# Stepper_Driver_Quark.net
KiCad netlist of a schematic drawn in Altium Designer
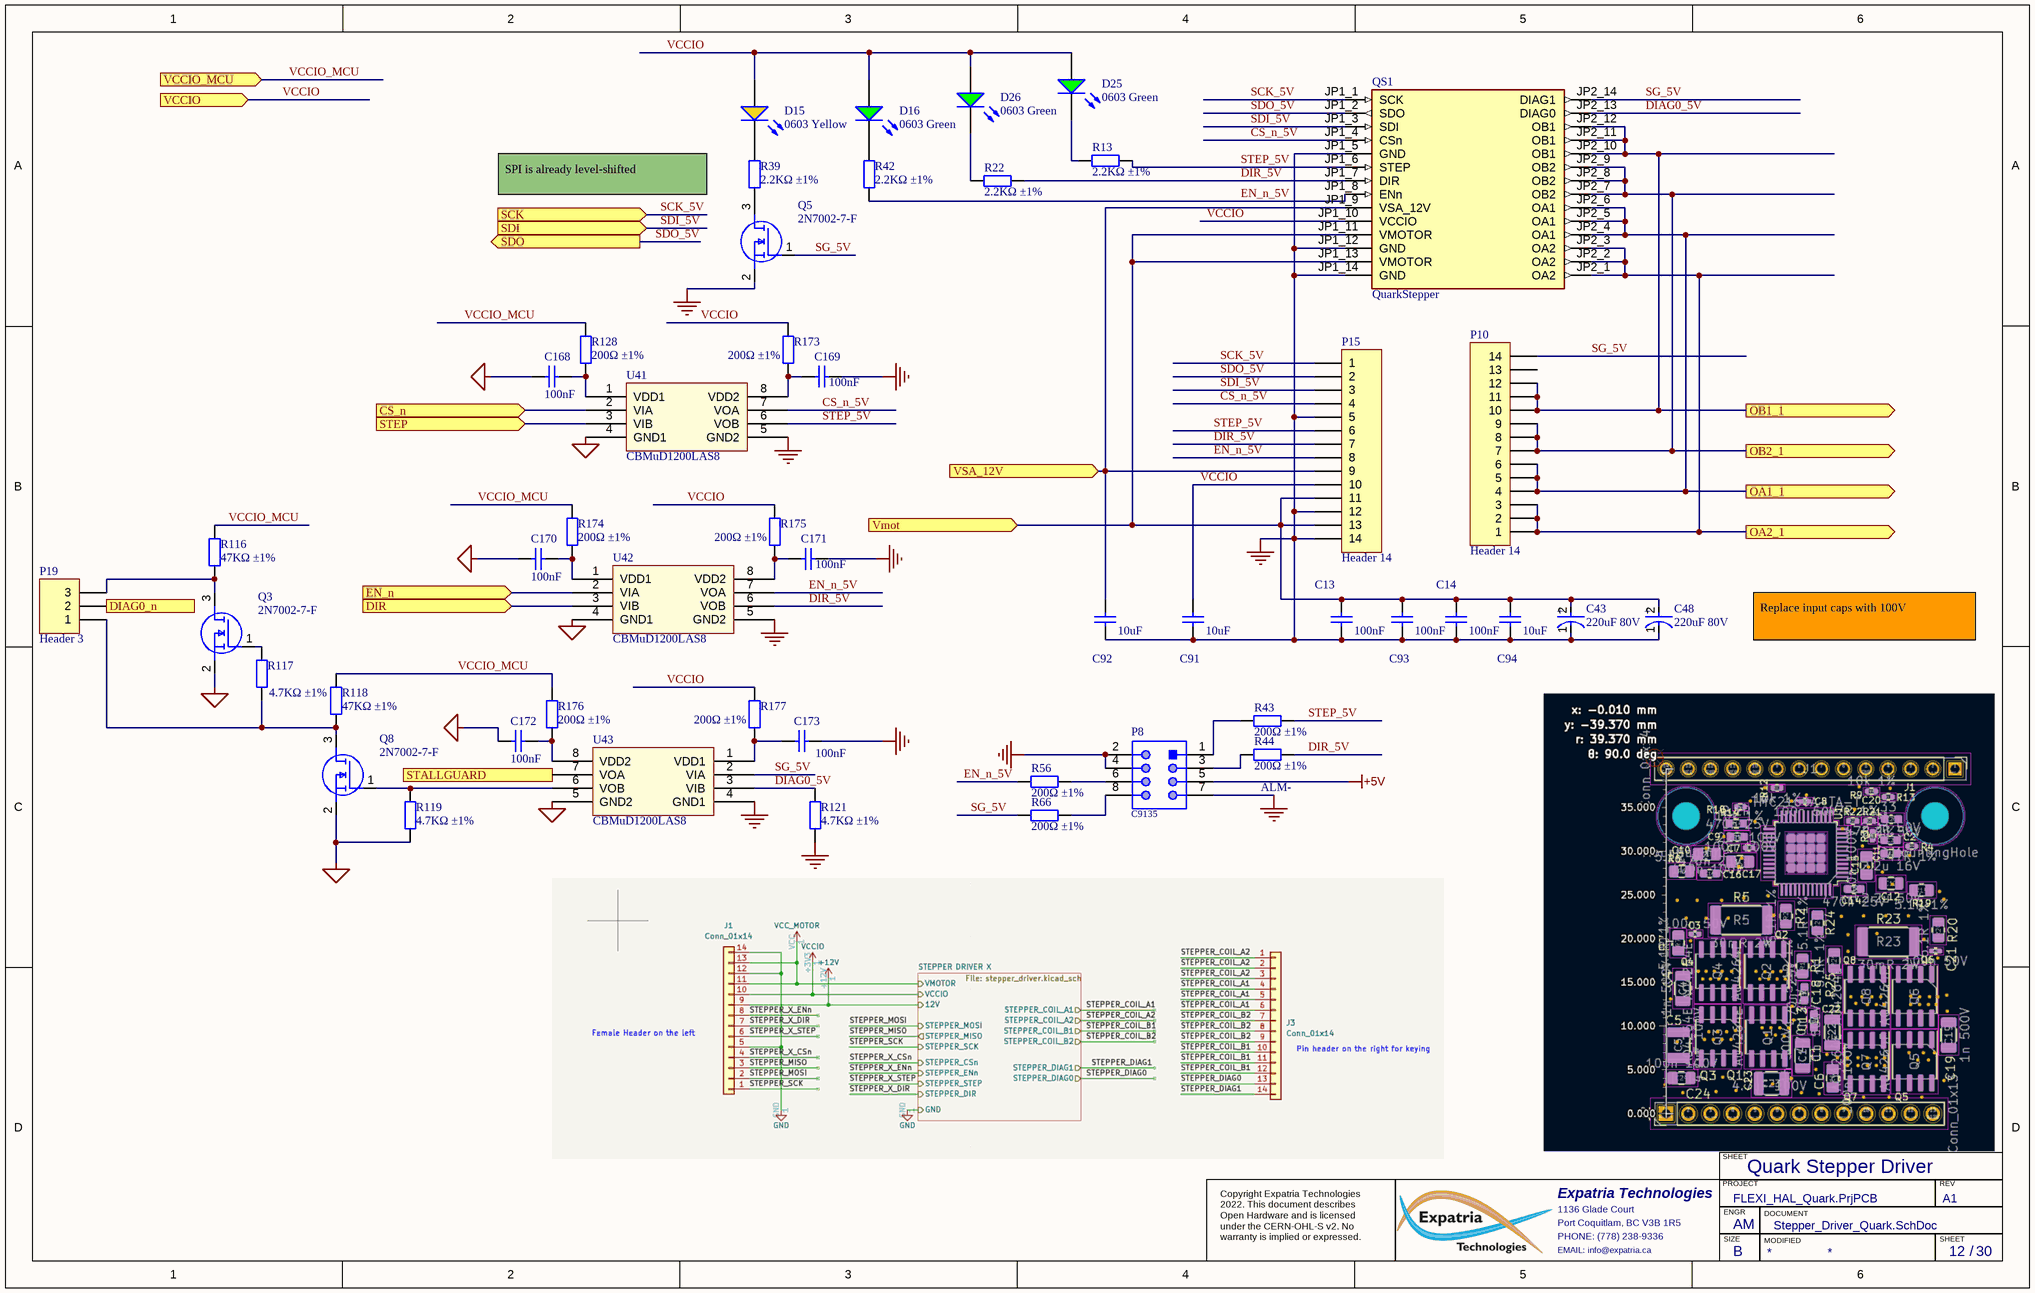
[diagram p0: Stepper_Driver_Quark.SchDoc]

(export (version "E")
  (design (tool "Eeschema 10.0.6"))
  (components
    (comp (ref "C13")
      (value "100nF")
      (footprint "0603_C")
      (description "Chip capacitors")
      (fields
        (field (name "MANUFACTURER") "YAGEO")
        (field (name "MANUFACTURER PART NUMBER") "CC0603KRX7R9BB104")
      )
      (libsource (lib "Cap") (part "0603 100nF (104) 10% 50V"))
    )
    (comp (ref "C14")
      (value "100nF")
      (footprint "0603_C")
      (description "Chip capacitors")
      (fields
        (field (name "MANUFACTURER") "YAGEO")
        (field (name "MANUFACTURER PART NUMBER") "CC0603KRX7R9BB104")
      )
      (libsource (lib "Cap") (part "0603 100nF (104) 10% 50V"))
    )
    (comp (ref "C43")
      (value "220uF 80V")
      (footprint "FP-RAD-TH-D_10_0_5-L_20_2-MFG")
      (description "Aluminum Electrolytic Capacitors (Radial Lead Type) AEC-Q200 Qualified 820uF ±20% 25V")
      (fields (field (name "TOLERANCE") "20%") (field (name "VOLTAGE") "25V"))
      (libsource (lib "Altium Content Vault") (part "203bc49f2ac43e59fd269a8c329ed05"))
    )
    (comp (ref "C48")
      (value "220uF 80V")
      (footprint "FP-RAD-TH-D_10_0_5-L_20_2-MFG")
      (description "Aluminum Electrolytic Capacitors (Radial Lead Type) AEC-Q200 Qualified 820uF ±20% 25V")
      (fields (field (name "TOLERANCE") "20%") (field (name "VOLTAGE") "25V"))
      (libsource (lib "Altium Content Vault") (part "203bc49f2ac43e59fd269a8c329ed05"))
    )
    (comp (ref "C91")
      (value "10uF")
      (footprint "0805_C")
      (description "Chip capacitors")
      (fields
        (field (name "MANUFACTURER") "Samsung Electro-Mechanics")
        (field (name "PARTNUMBER") "CL21A106KAYNNNE")
      )
      (libsource (lib "Cap") (part "0805 10uF (106) 10% 25V"))
    )
    (comp (ref "C92")
      (value "10uF")
      (footprint "0805_C")
      (description "Chip capacitors")
      (fields
        (field (name "MANUFACTURER") "Samsung Electro-Mechanics")
        (field (name "PARTNUMBER") "CL21A106KAYNNNE")
      )
      (libsource (lib "Cap") (part "0805 10uF (106) 10% 25V"))
    )
    (comp (ref "C93")
      (value "100nF")
      (footprint "0603_C")
      (description "Chip capacitors")
      (fields
        (field (name "MANUFACTURER") "YAGEO")
        (field (name "MANUFACTURER PART NUMBER") "CC0603KRX7R9BB104")
      )
      (libsource (lib "Cap") (part "0603 100nF (104) 10% 50V"))
    )
    (comp (ref "C94")
      (value "10uF")
      (footprint "0805_C")
      (description "Chip capacitors")
      (fields
        (field (name "MANUFACTURER") "Samsung Electro-Mechanics")
        (field (name "PARTNUMBER") "CL21A106KAYNNNE")
      )
      (libsource (lib "Cap") (part "0805 10uF (106) 10% 25V"))
    )
    (comp (ref "C168")
      (value "100nF")
      (footprint "0603_C")
      (description "Chip capacitors")
      (fields (field (name "MANUFACTURER") "YAGEO") (field (name "PARTNUMBER") "CC0603KRX7R9BB104"))
      (libsource (lib "Cap") (part "0603 100nF (104) 10% 50V"))
    )
    (comp (ref "C169")
      (value "100nF")
      (footprint "0603_C")
      (description "Chip capacitors")
      (fields (field (name "MANUFACTURER") "YAGEO") (field (name "PARTNUMBER") "CC0603KRX7R9BB104"))
      (libsource (lib "Cap") (part "0603 100nF (104) 10% 50V"))
    )
    (comp (ref "C170")
      (value "100nF")
      (footprint "0603_C")
      (description "Chip capacitors")
      (fields (field (name "MANUFACTURER") "YAGEO") (field (name "PARTNUMBER") "CC0603KRX7R9BB104"))
      (libsource (lib "Cap") (part "0603 100nF (104) 10% 50V"))
    )
    (comp (ref "C171")
      (value "100nF")
      (footprint "0603_C")
      (description "Chip capacitors")
      (fields (field (name "MANUFACTURER") "YAGEO") (field (name "PARTNUMBER") "CC0603KRX7R9BB104"))
      (libsource (lib "Cap") (part "0603 100nF (104) 10% 50V"))
    )
    (comp (ref "C172")
      (value "100nF")
      (footprint "0603_C")
      (description "Chip capacitors")
      (fields (field (name "MANUFACTURER") "YAGEO") (field (name "PARTNUMBER") "CC0603KRX7R9BB104"))
      (libsource (lib "Cap") (part "0603 100nF (104) 10% 50V"))
    )
    (comp (ref "C173")
      (value "100nF")
      (footprint "0603_C")
      (description "Chip capacitors")
      (fields (field (name "MANUFACTURER") "YAGEO") (field (name "PARTNUMBER") "CC0603KRX7R9BB104"))
      (libsource (lib "Cap") (part "0603 100nF (104) 10% 50V"))
    )
    (comp (ref "D15")
      (value "0603 Yellow")
      (footprint "0603_LED_S1")
      (description "LED")
      (libsource (lib "LED") (part "0603 LED Yellow"))
    )
    (comp (ref "D16")
      (value "0603 Green")
      (footprint "0603_LED_S1")
      (description "LED")
      (libsource (lib "LED") (part "0603 LED Green"))
    )
    (comp (ref "D25")
      (value "0603 Green")
      (footprint "0603_LED_S1")
      (description "LED")
      (libsource (lib "LED") (part "0603 LED Green"))
    )
    (comp (ref "D26")
      (value "0603 Green")
      (footprint "0603_LED_S1")
      (description "LED")
      (libsource (lib "LED") (part "0603 LED Green"))
    )
    (comp (ref "P8")
      (value "C9135")
      (footprint "61200821621")
      (description "Male Box Header WR-BHD, THT, Vertical, pitch 2.54 mm, 8 pins")
      (fields (field (name "MANUFACTURER") "Wurth Elektronik") (field (name "PUBLISHER") "WurthElektronik"))
      (libsource (lib "PrintNC_GRBLHAL_Breakout") (part "WE-CN-2P-M-R8"))
    )
    (comp (ref "P10")
      (value "Header 14")
      (footprint "HDR1X14")
      (description "Header, 14-Pin")
      (fields (field (name "PUBLISHER") "Altium Limited"))
      (libsource (lib "Miscellaneous Connectors") (part "Header 14"))
    )
    (comp (ref "P15")
      (value "Header 14")
      (footprint "HDR1X14")
      (description "Socket, 14-Pin")
      (fields (field (name "PUBLISHER") "Altium Limited"))
      (libsource (lib "") (part "Header 14_1"))
    )
    (comp (ref "P19")
      (value "Header 3")
      (footprint "HDR1X3")
      (description "Header, 3-Pin")
      (fields (field (name "PUBLISHER") "Altium Limited"))
      (libsource (lib "Miscellaneous Connectors") (part "Header 3"))
    )
    (comp (ref "Q3")
      (value "2N7002-7-F")
      (footprint "SOT-23(SOT-23-3)")
      (description "60V 115mA 7.5Ω@5V,50mA 370mW N Channel SOT-23 MOSFETs ROHS")
      (fields (field (name "MANUFACTURER") "Diodes Inc.") (field (name "MOUSER PART NUMBER") "621-2N7002-F"))
      (libsource (lib "Sienci_Labs") (part "2N7002-7-F"))
    )
    (comp (ref "Q5")
      (value "2N7002-7-F")
      (footprint "SOT-23(SOT-23-3)")
      (description "60V 115mA 7.5Ω@5V,50mA 370mW N Channel SOT-23 MOSFETs ROHS")
      (fields (field (name "MANUFACTURER") "Diodes Inc.") (field (name "MOUSER PART NUMBER") "621-2N7002-F"))
      (libsource (lib "Sienci_Labs") (part "2N7002-7-F"))
    )
    (comp (ref "Q8")
      (value "2N7002-7-F")
      (footprint "SOT-23(SOT-23-3)")
      (description "60V 115mA 7.5Ω@5V,50mA 370mW N Channel SOT-23 MOSFETs ROHS")
      (fields (field (name "MANUFACTURER") "Diodes Inc.") (field (name "MOUSER PART NUMBER") "621-2N7002-F"))
      (libsource (lib "Sienci_Labs") (part "2N7002-7-F"))
    )
    (comp (ref "QS1")
      (value "QuarkStepper")
      (footprint "QuarkStepperDriver")
      (description "Open source TMC2160 module")
      (fields
        (field (name "DIGI-KEY_PART_NUMBER") "1460-TMC2208SILENTSTEPSTICK-ND")
        (field (name "MF") "Trinamic Motion")
      )
      (libsource (lib "Universal_CNC_Breakout") (part "Quark_2160"))
    )
    (comp (ref "R13")
      (value "2.2KΩ ±1%")
      (footprint "0603_R")
      (description "Chip resistor")
      (fields (field (name "MANUFACTURER") "Uniroyal Elec") (field (name "POWER") "1/10W"))
      (libsource (lib "") (part "0603 2.2K (2201) 1%_1"))
    )
    (comp (ref "R22")
      (value "2.2KΩ ±1%")
      (footprint "0603_R")
      (description "Chip resistor")
      (fields (field (name "MANUFACTURER") "Uniroyal Elec") (field (name "POWER") "1/10W"))
      (libsource (lib "") (part "0603 2.2K (2201) 1%_1"))
    )
    (comp (ref "R39")
      (value "2.2KΩ ±1%")
      (footprint "0603_R")
      (description "Chip resistor")
      (fields (field (name "MANUFACTURER") "Uniroyal Elec") (field (name "POWER") "1/10W"))
      (libsource (lib "RES") (part "0603 2.2K (2201) 1%"))
    )
    (comp (ref "R42")
      (value "2.2KΩ ±1%")
      (footprint "0603_R")
      (description "Chip resistor")
      (fields (field (name "MANUFACTURER") "Uniroyal Elec") (field (name "POWER") "1/10W"))
      (libsource (lib "RES") (part "0603 2.2K (2201) 1%"))
    )
    (comp (ref "R43")
      (value "200Ω ±1%")
      (footprint "0603_R")
      (description "Chip resistor")
      (fields (field (name "MANUFACTURER") "Uniroyal Elec") (field (name "PARTNUMBER") "0603WAF2000T5E"))
      (libsource (lib "") (part "0603 200R (2000) 1%_1"))
    )
    (comp (ref "R44")
      (value "200Ω ±1%")
      (footprint "0603_R")
      (description "Chip resistor")
      (fields (field (name "MANUFACTURER") "Uniroyal Elec") (field (name "PARTNUMBER") "0603WAF2000T5E"))
      (libsource (lib "") (part "0603 200R (2000) 1%_1"))
    )
    (comp (ref "R56")
      (value "200Ω ±1%")
      (footprint "0603_R")
      (description "Chip resistor")
      (fields (field (name "MANUFACTURER") "Uniroyal Elec") (field (name "PARTNUMBER") "0603WAF2000T5E"))
      (libsource (lib "") (part "0603 200R (2000) 1%_1"))
    )
    (comp (ref "R66")
      (value "200Ω ±1%")
      (footprint "0603_R")
      (description "Chip resistor")
      (fields (field (name "MANUFACTURER") "Uniroyal Elec") (field (name "PARTNUMBER") "0603WAF2000T5E"))
      (libsource (lib "") (part "0603 200R (2000) 1%_1"))
    )
    (comp (ref "R116")
      (value "47KΩ ±1%")
      (footprint "0603_R")
      (description "Chip resistor")
      (fields (field (name "MANUFACTURER") "Uniroyal Elec") (field (name "PARTNUMBER") "0603WAF4702T5E"))
      (libsource (lib "RES") (part "0603 47K (4702) 1%"))
    )
    (comp (ref "R117")
      (value "4.7KΩ ±1%")
      (footprint "0603_R")
      (description "Chip resistor")
      (fields (field (name "MANUFACTURER") "Uniroyal Elec") (field (name "PARTNUMBER") "0603WAF4701T5E"))
      (libsource (lib "RES") (part "0603 4.7K (4701) 1%"))
    )
    (comp (ref "R118")
      (value "47KΩ ±1%")
      (footprint "0603_R")
      (description "Chip resistor")
      (fields (field (name "MANUFACTURER") "Uniroyal Elec") (field (name "PARTNUMBER") "0603WAF4702T5E"))
      (libsource (lib "RES") (part "0603 47K (4702) 1%"))
    )
    (comp (ref "R119")
      (value "4.7KΩ ±1%")
      (footprint "0603_R")
      (description "Chip resistor")
      (fields (field (name "MANUFACTURER") "Uniroyal Elec") (field (name "PARTNUMBER") "0603WAF4701T5E"))
      (libsource (lib "RES") (part "0603 4.7K (4701) 1%"))
    )
    (comp (ref "R121")
      (value "4.7KΩ ±1%")
      (footprint "0603_R")
      (description "Chip resistor")
      (fields (field (name "MANUFACTURER") "Uniroyal Elec") (field (name "PARTNUMBER") "0603WAF4701T5E"))
      (libsource (lib "RES") (part "0603 4.7K (4701) 1%"))
    )
    (comp (ref "R128")
      (value "200Ω ±1%")
      (footprint "0603_R")
      (description "Chip resistor")
      (fields (field (name "MANUFACTURER") "Uniroyal Elec") (field (name "PARTNUMBER") "0603WAF2000T5E"))
      (libsource (lib "RES") (part "0603 200R (2000) 1%"))
    )
    (comp (ref "R173")
      (value "200Ω ±1%")
      (footprint "0603_R")
      (description "Chip resistor")
      (fields (field (name "MANUFACTURER") "Uniroyal Elec") (field (name "PARTNUMBER") "0603WAF2000T5E"))
      (libsource (lib "RES") (part "0603 200R (2000) 1%"))
    )
    (comp (ref "R174")
      (value "200Ω ±1%")
      (footprint "0603_R")
      (description "Chip resistor")
      (fields (field (name "MANUFACTURER") "Uniroyal Elec") (field (name "PARTNUMBER") "0603WAF2000T5E"))
      (libsource (lib "RES") (part "0603 200R (2000) 1%"))
    )
    (comp (ref "R175")
      (value "200Ω ±1%")
      (footprint "0603_R")
      (description "Chip resistor")
      (fields (field (name "MANUFACTURER") "Uniroyal Elec") (field (name "PARTNUMBER") "0603WAF2000T5E"))
      (libsource (lib "RES") (part "0603 200R (2000) 1%"))
    )
    (comp (ref "R176")
      (value "200Ω ±1%")
      (footprint "0603_R")
      (description "Chip resistor")
      (fields (field (name "MANUFACTURER") "Uniroyal Elec") (field (name "PARTNUMBER") "0603WAF2000T5E"))
      (libsource (lib "") (part "0603 200R (2000) 1%_2"))
    )
    (comp (ref "R177")
      (value "200Ω ±1%")
      (footprint "0603_R")
      (description "Chip resistor")
      (fields (field (name "MANUFACTURER") "Uniroyal Elec") (field (name "PARTNUMBER") "0603WAF2000T5E"))
      (libsource (lib "") (part "0603 200R (2000) 1%_2"))
    )
    (comp (ref "U41")
      (value "CBMuD1200LAS8")
      (footprint "SOIC-8_150mil")
      (description "Dual Channel Isolator")
      (libsource (lib "IC") (part "CBMuD1200LAS8"))
    )
    (comp (ref "U42")
      (value "CBMuD1200LAS8")
      (footprint "SOIC-8_150mil")
      (description "Dual Channel Isolator")
      (libsource (lib "IC") (part "CBMuD1200LAS8"))
    )
    (comp (ref "U43")
      (value "CBMuD1200LAS8")
      (footprint "SOIC-8_150mil")
      (description "Dual Channel Isolator")
      (libsource (lib "") (part "CBMuD1200LAS8_1"))
    )
  )
  (nets
    (net (code "1") (name "+5V") (class "Default")
      (node (ref "P8") (pin "5") (pinfunction "5_5") (pintype "passive"))
    )
    (net (code "2") (name "/CS_n") (class "Default")
      (node (ref "U41") (pin "2") (pinfunction "VIA_2") (pintype "passive"))
    )
    (net (code "3") (name "/CS_n_5V") (class "Default")
      (node (ref "P15") (pin "4") (pinfunction "4_4") (pintype "passive"))
      (node (ref "QS1") (pin "JP1_4") (pinfunction "CSn_JP1_4") (pintype "input"))
      (node (ref "U41") (pin "7") (pinfunction "VOA_7") (pintype "passive"))
    )
    (net (code "4") (name "/DIAG0_5V") (class "Default")
      (node (ref "QS1") (pin "JP2_13") (pinfunction "DIAG0_JP2_13") (pintype "output"))
      (node (ref "R121") (pin "2") (pinfunction "2_2") (pintype "passive"))
      (node (ref "U43") (pin "3") (pinfunction "VIB_3") (pintype "passive"))
    )
    (net (code "5") (name "/DIAG0_n") (class "Default")
      (node (ref "P19") (pin "2") (pinfunction "2_2") (pintype "passive"))
    )
    (net (code "6") (name "/DIR") (class "Default")
      (node (ref "U42") (pin "3") (pinfunction "VIB_3") (pintype "passive"))
    )
    (net (code "7") (name "/DIR_5V") (class "Default")
      (node (ref "P15") (pin "7") (pinfunction "7_7") (pintype "passive"))
      (node (ref "QS1") (pin "JP1_7") (pinfunction "DIR_JP1_7") (pintype "input"))
      (node (ref "R22") (pin "1") (pinfunction "1_1") (pintype "passive"))
      (node (ref "R44") (pin "1") (pinfunction "1_1") (pintype "passive"))
      (node (ref "U42") (pin "6") (pinfunction "VOB_6") (pintype "passive"))
    )
    (net (code "8") (name "/EN_n") (class "Default")
      (node (ref "U42") (pin "2") (pinfunction "VIA_2") (pintype "passive"))
    )
    (net (code "9") (name "/EN_n_5V") (class "Default")
      (node (ref "P15") (pin "8") (pinfunction "8_8") (pintype "passive"))
      (node (ref "QS1") (pin "JP1_8") (pinfunction "ENn_JP1_8") (pintype "input"))
      (node (ref "R42") (pin "1") (pinfunction "1_1") (pintype "passive"))
      (node (ref "R56") (pin "2") (pinfunction "2_2") (pintype "passive"))
      (node (ref "U42") (pin "7") (pinfunction "VOA_7") (pintype "passive"))
    )
    (net (code "10") (name "/OA1_1") (class "Default")
      (node (ref "P10") (pin "4") (pinfunction "4_4") (pintype "passive"))
      (node (ref "P10") (pin "5") (pinfunction "5_5") (pintype "passive"))
      (node (ref "P10") (pin "6") (pinfunction "6_6") (pintype "passive"))
      (node (ref "QS1") (pin "JP2_4") (pinfunction "OA1_JP2_4") (pintype "output"))
      (node (ref "QS1") (pin "JP2_5") (pinfunction "OA1_JP2_5") (pintype "output"))
      (node (ref "QS1") (pin "JP2_6") (pinfunction "OA1_JP2_6") (pintype "output"))
    )
    (net (code "11") (name "/OA2_1") (class "Default")
      (node (ref "P10") (pin "1") (pinfunction "1_1") (pintype "passive"))
      (node (ref "P10") (pin "2") (pinfunction "2_2") (pintype "passive"))
      (node (ref "P10") (pin "3") (pinfunction "3_3") (pintype "passive"))
      (node (ref "QS1") (pin "JP2_1") (pinfunction "OA2_JP2_1") (pintype "output"))
      (node (ref "QS1") (pin "JP2_2") (pinfunction "OA2_JP2_2") (pintype "output"))
      (node (ref "QS1") (pin "JP2_3") (pinfunction "OA2_JP2_3") (pintype "output"))
    )
    (net (code "12") (name "/OB1_1") (class "Default")
      (node (ref "P10") (pin "10") (pinfunction "10_10") (pintype "passive"))
      (node (ref "P10") (pin "11") (pinfunction "11_11") (pintype "passive"))
      (node (ref "P10") (pin "12") (pinfunction "12_12") (pintype "passive"))
      (node (ref "QS1") (pin "JP2_10") (pinfunction "OB1_JP2_10") (pintype "output"))
      (node (ref "QS1") (pin "JP2_11") (pinfunction "OB1_JP2_11") (pintype "output"))
      (node (ref "QS1") (pin "JP2_12") (pinfunction "OB1_JP2_12") (pintype "output"))
    )
    (net (code "13") (name "/OB2_1") (class "Default")
      (node (ref "P10") (pin "7") (pinfunction "7_7") (pintype "passive"))
      (node (ref "P10") (pin "8") (pinfunction "8_8") (pintype "passive"))
      (node (ref "P10") (pin "9") (pinfunction "9_9") (pintype "passive"))
      (node (ref "QS1") (pin "JP2_7") (pinfunction "OB2_JP2_7") (pintype "output"))
      (node (ref "QS1") (pin "JP2_8") (pinfunction "OB2_JP2_8") (pintype "output"))
      (node (ref "QS1") (pin "JP2_9") (pinfunction "OB2_JP2_9") (pintype "output"))
    )
    (net (code "14") (name "/SCK_5V") (class "Default")
      (node (ref "P15") (pin "1") (pinfunction "1_1") (pintype "passive"))
      (node (ref "QS1") (pin "JP1_1") (pinfunction "SCK_JP1_1") (pintype "input"))
    )
    (net (code "15") (name "/SDI_5V") (class "Default")
      (node (ref "P15") (pin "3") (pinfunction "3_3") (pintype "passive"))
      (node (ref "QS1") (pin "JP1_3") (pinfunction "SDI_JP1_3") (pintype "input"))
    )
    (net (code "16") (name "/SDO_5V") (class "Default")
      (node (ref "P15") (pin "2") (pinfunction "2_2") (pintype "passive"))
      (node (ref "QS1") (pin "JP1_2") (pinfunction "SDO_JP1_2") (pintype "output"))
    )
    (net (code "17") (name "/SG_5V") (class "Default")
      (node (ref "P10") (pin "14") (pinfunction "14_14") (pintype "passive"))
      (node (ref "Q5") (pin "1") (pinfunction "G_1") (pintype "passive"))
      (node (ref "QS1") (pin "JP2_14") (pinfunction "DIAG1_JP2_14") (pintype "output"))
      (node (ref "R66") (pin "2") (pinfunction "2_2") (pintype "passive"))
      (node (ref "U43") (pin "2") (pinfunction "VIA_2") (pintype "passive"))
    )
    (net (code "18") (name "/STALLGUARD") (class "Default")
      (node (ref "U43") (pin "7") (pinfunction "VOA_7") (pintype "passive"))
    )
    (net (code "19") (name "/STEP") (class "Default")
      (node (ref "U41") (pin "3") (pinfunction "VIB_3") (pintype "passive"))
    )
    (net (code "20") (name "/STEP_5V") (class "Default")
      (node (ref "P15") (pin "6") (pinfunction "6_6") (pintype "passive"))
      (node (ref "QS1") (pin "JP1_6") (pinfunction "STEP_JP1_6") (pintype "input"))
      (node (ref "R13") (pin "1") (pinfunction "1_1") (pintype "passive"))
      (node (ref "R43") (pin "1") (pinfunction "1_1") (pintype "passive"))
      (node (ref "U41") (pin "6") (pinfunction "VOB_6") (pintype "passive"))
    )
    (net (code "21") (name "/VCCIO") (class "Default")
      (node (ref "C91") (pin "2") (pinfunction "2_2") (pintype "passive"))
      (node (ref "D15") (pin "A") (pinfunction "A_A") (pintype "passive"))
      (node (ref "D16") (pin "A") (pinfunction "A_A") (pintype "passive"))
      (node (ref "D25") (pin "A") (pinfunction "A_A") (pintype "passive"))
      (node (ref "D26") (pin "A") (pinfunction "A_A") (pintype "passive"))
      (node (ref "P15") (pin "10") (pinfunction "10_10") (pintype "passive"))
      (node (ref "QS1") (pin "JP1_10") (pinfunction "VCCIO_JP1_10") (pintype "passive"))
      (node (ref "R173") (pin "2") (pinfunction "2_2") (pintype "passive"))
      (node (ref "R175") (pin "2") (pinfunction "2_2") (pintype "passive"))
      (node (ref "R177") (pin "2") (pinfunction "2_2") (pintype "passive"))
    )
    (net (code "22") (name "/VCCIO_MCU") (class "Default")
      (node (ref "R116") (pin "2") (pinfunction "2_2") (pintype "passive"))
      (node (ref "R118") (pin "2") (pinfunction "2_2") (pintype "passive"))
      (node (ref "R128") (pin "2") (pinfunction "2_2") (pintype "passive"))
      (node (ref "R174") (pin "2") (pinfunction "2_2") (pintype "passive"))
      (node (ref "R176") (pin "2") (pinfunction "2_2") (pintype "passive"))
    )
    (net (code "23") (name "/VSA_12V") (class "Default")
      (node (ref "C92") (pin "2") (pinfunction "2_2") (pintype "passive"))
      (node (ref "P15") (pin "9") (pinfunction "9_9") (pintype "passive"))
      (node (ref "QS1") (pin "JP1_9") (pinfunction "VSA_12V_JP1_9") (pintype "passive"))
    )
    (net (code "24") (name "/Vmot") (class "Default")
      (node (ref "C13") (pin "1") (pinfunction "1_1") (pintype "passive"))
      (node (ref "C14") (pin "1") (pinfunction "1_1") (pintype "passive"))
      (node (ref "C43") (pin "2") (pinfunction "A_2") (pintype "passive"))
      (node (ref "C48") (pin "2") (pinfunction "A_2") (pintype "passive"))
      (node (ref "C93") (pin "1") (pinfunction "1_1") (pintype "passive"))
      (node (ref "C94") (pin "2") (pinfunction "2_2") (pintype "passive"))
      (node (ref "P15") (pin "11") (pinfunction "11_11") (pintype "passive"))
      (node (ref "P15") (pin "13") (pinfunction "13_13") (pintype "passive"))
      (node (ref "QS1") (pin "JP1_11") (pinfunction "VMOTOR_JP1_11") (pintype "passive"))
      (node (ref "QS1") (pin "JP1_13") (pinfunction "VMOTOR_JP1_13") (pintype "passive"))
    )
    (net (code "25") (name "GND") (class "Default")
      (node (ref "C13") (pin "2") (pinfunction "2_2") (pintype "passive"))
      (node (ref "C14") (pin "2") (pinfunction "2_2") (pintype "passive"))
      (node (ref "C169") (pin "1") (pinfunction "1_1") (pintype "passive"))
      (node (ref "C171") (pin "1") (pinfunction "1_1") (pintype "passive"))
      (node (ref "C173") (pin "2") (pinfunction "2_2") (pintype "passive"))
      (node (ref "C43") (pin "1") (pinfunction "C_1") (pintype "passive"))
      (node (ref "C48") (pin "1") (pinfunction "C_1") (pintype "passive"))
      (node (ref "C91") (pin "1") (pinfunction "1_1") (pintype "passive"))
      (node (ref "C92") (pin "1") (pinfunction "1_1") (pintype "passive"))
      (node (ref "C93") (pin "2") (pinfunction "2_2") (pintype "passive"))
      (node (ref "C94") (pin "1") (pinfunction "1_1") (pintype "passive"))
      (node (ref "P15") (pin "12") (pinfunction "12_12") (pintype "passive"))
      (node (ref "P15") (pin "14") (pinfunction "14_14") (pintype "passive"))
      (node (ref "P15") (pin "5") (pinfunction "5_5") (pintype "passive"))
      (node (ref "P8") (pin "2") (pinfunction "2_2") (pintype "passive"))
      (node (ref "P8") (pin "4") (pinfunction "4_4") (pintype "passive"))
      (node (ref "P8") (pin "7") (pinfunction "7_7") (pintype "passive"))
      (node (ref "Q5") (pin "2") (pinfunction "S_2") (pintype "passive"))
      (node (ref "QS1") (pin "JP1_12") (pinfunction "GND_JP1_12") (pintype "passive"))
      (node (ref "QS1") (pin "JP1_14") (pinfunction "GND_JP1_14") (pintype "passive"))
      (node (ref "QS1") (pin "JP1_5") (pinfunction "GND_JP1_5") (pintype "passive"))
      (node (ref "R121") (pin "1") (pinfunction "1_1") (pintype "passive"))
      (node (ref "U41") (pin "5") (pinfunction "GND2_5") (pintype "passive"))
      (node (ref "U42") (pin "5") (pinfunction "GND2_5") (pintype "passive"))
      (node (ref "U43") (pin "4") (pinfunction "GND1_4") (pintype "passive"))
    )
    (net (code "26") (name "MCU_GND") (class "Default")
      (node (ref "C168") (pin "2") (pinfunction "2_2") (pintype "passive"))
      (node (ref "C170") (pin "2") (pinfunction "2_2") (pintype "passive"))
      (node (ref "C172") (pin "1") (pinfunction "1_1") (pintype "passive"))
      (node (ref "Q3") (pin "2") (pinfunction "S_2") (pintype "passive"))
      (node (ref "Q8") (pin "2") (pinfunction "S_2") (pintype "passive"))
      (node (ref "R119") (pin "1") (pinfunction "1_1") (pintype "passive"))
      (node (ref "U41") (pin "4") (pinfunction "GND1_4") (pintype "passive"))
      (node (ref "U42") (pin "4") (pinfunction "GND1_4") (pintype "passive"))
      (node (ref "U43") (pin "5") (pinfunction "GND2_5") (pintype "passive"))
    )
    (net (code "27") (name "Net-(D15-PadK)") (class "Default")
      (node (ref "D15") (pin "K") (pinfunction "K_K") (pintype "passive"))
      (node (ref "R39") (pin "2") (pinfunction "2_2") (pintype "passive"))
    )
    (net (code "28") (name "Net-(D16-PadK)") (class "Default")
      (node (ref "D16") (pin "K") (pinfunction "K_K") (pintype "passive"))
      (node (ref "R42") (pin "2") (pinfunction "2_2") (pintype "passive"))
    )
    (net (code "29") (name "Net-(D25-PadK)") (class "Default")
      (node (ref "D25") (pin "K") (pinfunction "K_K") (pintype "passive"))
      (node (ref "R13") (pin "2") (pinfunction "2_2") (pintype "passive"))
    )
    (net (code "30") (name "Net-(D26-PadK)") (class "Default")
      (node (ref "D26") (pin "K") (pinfunction "K_K") (pintype "passive"))
      (node (ref "R22") (pin "2") (pinfunction "2_2") (pintype "passive"))
    )
    (net (code "31") (name "Net-(P8-Pad1)") (class "Default")
      (node (ref "P8") (pin "1") (pinfunction "1_1") (pintype "passive"))
      (node (ref "R43") (pin "2") (pinfunction "2_2") (pintype "passive"))
    )
    (net (code "32") (name "Net-(P8-Pad3)") (class "Default")
      (node (ref "P8") (pin "3") (pinfunction "3_3") (pintype "passive"))
      (node (ref "R44") (pin "2") (pinfunction "2_2") (pintype "passive"))
    )
    (net (code "33") (name "Net-(P8-Pad6)") (class "Default")
      (node (ref "P8") (pin "6") (pinfunction "6_6") (pintype "passive"))
      (node (ref "R56") (pin "1") (pinfunction "1_1") (pintype "passive"))
    )
    (net (code "34") (name "Net-(P8-Pad8)") (class "Default")
      (node (ref "P8") (pin "8") (pinfunction "8_8") (pintype "passive"))
      (node (ref "R66") (pin "1") (pinfunction "1_1") (pintype "passive"))
    )
    (net (code "35") (name "Net-(Q3-D)") (class "Default")
      (node (ref "P19") (pin "3") (pinfunction "3_3") (pintype "passive"))
      (node (ref "Q3") (pin "3") (pinfunction "D_3") (pintype "passive"))
      (node (ref "R116") (pin "1") (pinfunction "1_1") (pintype "passive"))
    )
    (net (code "36") (name "Net-(Q3-G)") (class "Default")
      (node (ref "Q3") (pin "1") (pinfunction "G_1") (pintype "passive"))
      (node (ref "R117") (pin "2") (pinfunction "2_2") (pintype "passive"))
    )
    (net (code "37") (name "Net-(Q5-D)") (class "Default")
      (node (ref "Q5") (pin "3") (pinfunction "D_3") (pintype "passive"))
      (node (ref "R39") (pin "1") (pinfunction "1_1") (pintype "passive"))
    )
    (net (code "38") (name "Net-(Q8-D)") (class "Default")
      (node (ref "P19") (pin "1") (pinfunction "1_1") (pintype "passive"))
      (node (ref "Q8") (pin "3") (pinfunction "D_3") (pintype "passive"))
      (node (ref "R117") (pin "1") (pinfunction "1_1") (pintype "passive"))
      (node (ref "R118") (pin "1") (pinfunction "1_1") (pintype "passive"))
    )
    (net (code "39") (name "Net-(Q8-G)") (class "Default")
      (node (ref "Q8") (pin "1") (pinfunction "G_1") (pintype "passive"))
      (node (ref "R119") (pin "2") (pinfunction "2_2") (pintype "passive"))
      (node (ref "U43") (pin "6") (pinfunction "VOB_6") (pintype "passive"))
    )
    (net (code "40") (name "Net-(U41-VDD1)") (class "Default")
      (node (ref "C168") (pin "1") (pinfunction "1_1") (pintype "passive"))
      (node (ref "R128") (pin "1") (pinfunction "1_1") (pintype "passive"))
      (node (ref "U41") (pin "1") (pinfunction "VDD1_1") (pintype "passive"))
    )
    (net (code "41") (name "Net-(U41-VDD2)") (class "Default")
      (node (ref "C169") (pin "2") (pinfunction "2_2") (pintype "passive"))
      (node (ref "R173") (pin "1") (pinfunction "1_1") (pintype "passive"))
      (node (ref "U41") (pin "8") (pinfunction "VDD2_8") (pintype "passive"))
    )
    (net (code "42") (name "Net-(U42-VDD1)") (class "Default")
      (node (ref "C170") (pin "1") (pinfunction "1_1") (pintype "passive"))
      (node (ref "R174") (pin "1") (pinfunction "1_1") (pintype "passive"))
      (node (ref "U42") (pin "1") (pinfunction "VDD1_1") (pintype "passive"))
    )
    (net (code "43") (name "Net-(U42-VDD2)") (class "Default")
      (node (ref "C171") (pin "2") (pinfunction "2_2") (pintype "passive"))
      (node (ref "R175") (pin "1") (pinfunction "1_1") (pintype "passive"))
      (node (ref "U42") (pin "8") (pinfunction "VDD2_8") (pintype "passive"))
    )
    (net (code "44") (name "Net-(U43-VDD1)") (class "Default")
      (node (ref "C173") (pin "1") (pinfunction "1_1") (pintype "passive"))
      (node (ref "R177") (pin "1") (pinfunction "1_1") (pintype "passive"))
      (node (ref "U43") (pin "1") (pinfunction "VDD1_1") (pintype "passive"))
    )
    (net (code "45") (name "Net-(U43-VDD2)") (class "Default")
      (node (ref "C172") (pin "2") (pinfunction "2_2") (pintype "passive"))
      (node (ref "R176") (pin "1") (pinfunction "1_1") (pintype "passive"))
      (node (ref "U43") (pin "8") (pinfunction "VDD2_8") (pintype "passive"))
    )
    (net (code "46") (name "unconnected-(P10-Pad13)") (class "Default")
      (node (ref "P10") (pin "13") (pinfunction "13_13") (pintype "passive"))
    )
  )
)
